# F.net
KiCad netlist of a schematic drawn in Altium Designer
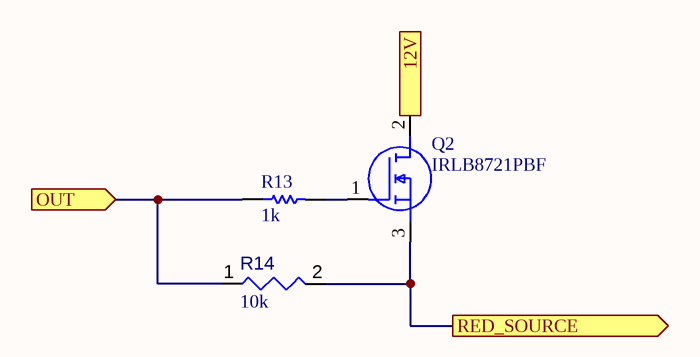
[diagram p0: F.SchDoc]

(export (version "E")
  (design (tool "Eeschema 10.0.6"))
  (components
    (comp (ref "Q2")
      (value "IRLB8721PBF")
      (footprint "SamacSys:TO254P483X1016X1994-3P")
      (description "MOSFET (N-Channel)")
      (fields (field (name "MOUSER PART NUMBER") "942-IRLB8721PBF"))
      (libsource (lib "*") (part "IRLB8721PBF"))
    )
    (comp (ref "R13")
      (value "1k")
      (footprint "RESC3116X70X50ML13T20")
      (description "Chip Resistor, 1 KOhm, +/- 1%, 0.25 W, -55 to 155 degC, 1206 (3216 Metric)")
      (fields (field (name "TOLERANCE") "1%") (field (name "POWER") "250mW"))
      (libsource (lib "") (part "RES-2_1"))
    )
    (comp (ref "R14")
      (value "10k")
      (footprint "RESC2013X50X35ML15T15")
      (description "Chip Resistor, 10 KOhm, +/- 1%, 125 mW, -55 to 155 degC, 0805 (2012 Metric)")
      (fields (field (name "TOLERANCE") "1%") (field (name "POWER") "125mW"))
      (libsource (lib "Hector Dela Rosa") (part "RES-2"))
    )
  )
  (nets
    (net (code "1") (name "/12V") (class "Default")
      (node (ref "Q2") (pin "2") (pinfunction "D_2") (pintype "passive"))
    )
    (net (code "2") (name "/OUT") (class "Default")
      (node (ref "R13") (pin "1") (pinfunction "1_1") (pintype "passive"))
      (node (ref "R14") (pin "1") (pinfunction "1_1") (pintype "passive"))
    )
    (net (code "3") (name "/RED_SOURCE") (class "Default")
      (node (ref "Q2") (pin "3") (pinfunction "S_3") (pintype "passive"))
      (node (ref "R14") (pin "2") (pinfunction "2_2") (pintype "passive"))
    )
    (net (code "4") (name "Net-(Q2-G)") (class "Default")
      (node (ref "Q2") (pin "1") (pinfunction "G_1") (pintype "passive"))
      (node (ref "R13") (pin "2") (pinfunction "2_2") (pintype "passive"))
    )
  )
)
